# JumpingJack.net
KiCad netlist of a schematic drawn in EasyEDA Pro
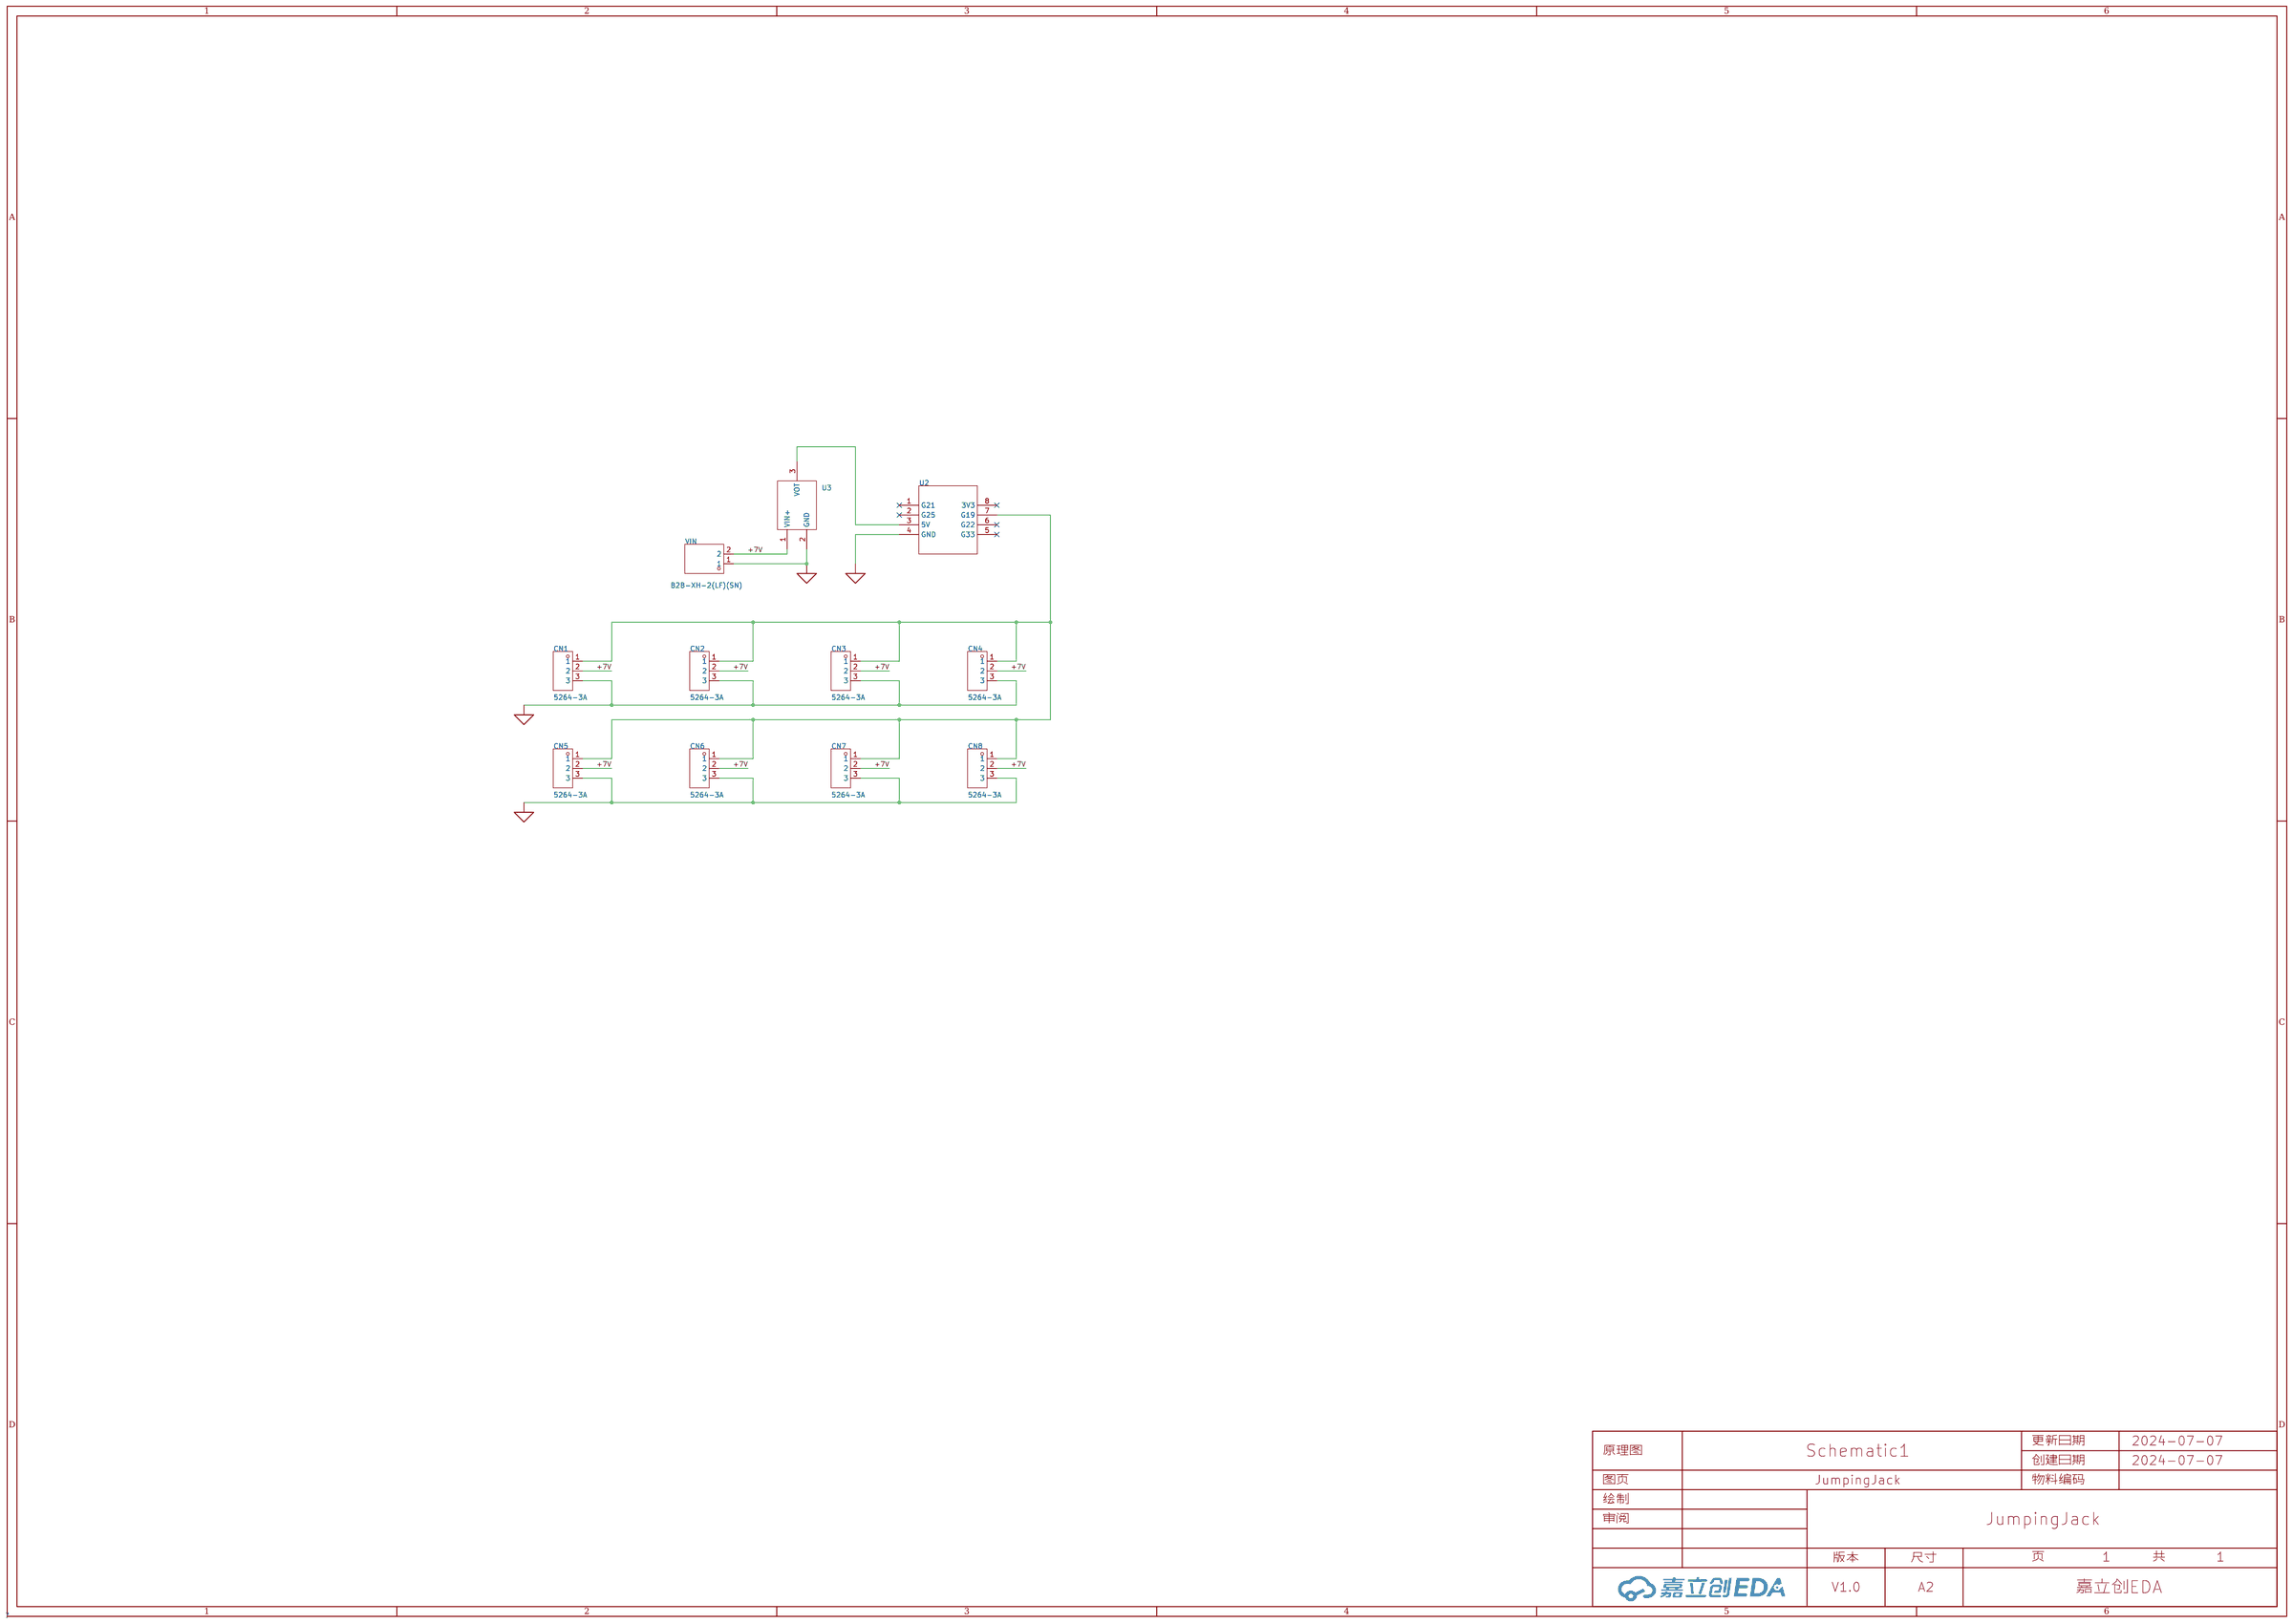
[diagram p0: schematic sheet]

(export (version "E")
  (design (tool "Eeschema 10.0.6"))
  (components
    (comp (ref "CN1")
      (value "5264-3A")
      (footprint "easyedapro:CONN-TH_5264-3A")
      (description "插针结构:1x3P;间距:2.5mm;安装方式:-;参考系列:-;总PIN数:3P;排数:1;每排PIN数:3;行距:-;触头材质:-;")
      (fields (field (name "Manufacturer") "BOOMELE(博穆精密)"))
      (libsource (lib "easyedapro") (part "5264-3A"))
    )
    (comp (ref "CN2")
      (value "5264-3A")
      (footprint "easyedapro:CONN-TH_5264-3A")
      (description "插针结构:1x3P;间距:2.5mm;安装方式:-;参考系列:-;总PIN数:3P;排数:1;每排PIN数:3;行距:-;触头材质:-;")
      (fields (field (name "Manufacturer") "BOOMELE(博穆精密)"))
      (libsource (lib "easyedapro") (part "5264-3A"))
    )
    (comp (ref "CN3")
      (value "5264-3A")
      (footprint "easyedapro:CONN-TH_5264-3A")
      (description "插针结构:1x3P;间距:2.5mm;安装方式:-;参考系列:-;总PIN数:3P;排数:1;每排PIN数:3;行距:-;触头材质:-;")
      (fields (field (name "Manufacturer") "BOOMELE(博穆精密)"))
      (libsource (lib "easyedapro") (part "5264-3A"))
    )
    (comp (ref "CN4")
      (value "5264-3A")
      (footprint "easyedapro:CONN-TH_5264-3A")
      (description "插针结构:1x3P;间距:2.5mm;安装方式:-;参考系列:-;总PIN数:3P;排数:1;每排PIN数:3;行距:-;触头材质:-;")
      (fields (field (name "Manufacturer") "BOOMELE(博穆精密)"))
      (libsource (lib "easyedapro") (part "5264-3A"))
    )
    (comp (ref "CN5")
      (value "5264-3A")
      (footprint "easyedapro:CONN-TH_5264-3A")
      (description "插针结构:1x3P;间距:2.5mm;安装方式:-;参考系列:-;总PIN数:3P;排数:1;每排PIN数:3;行距:-;触头材质:-;")
      (fields (field (name "Manufacturer") "BOOMELE(博穆精密)"))
      (libsource (lib "easyedapro") (part "5264-3A"))
    )
    (comp (ref "CN6")
      (value "5264-3A")
      (footprint "easyedapro:CONN-TH_5264-3A")
      (description "插针结构:1x3P;间距:2.5mm;安装方式:-;参考系列:-;总PIN数:3P;排数:1;每排PIN数:3;行距:-;触头材质:-;")
      (fields (field (name "Manufacturer") "BOOMELE(博穆精密)"))
      (libsource (lib "easyedapro") (part "5264-3A"))
    )
    (comp (ref "CN7")
      (value "5264-3A")
      (footprint "easyedapro:CONN-TH_5264-3A")
      (description "插针结构:1x3P;间距:2.5mm;安装方式:-;参考系列:-;总PIN数:3P;排数:1;每排PIN数:3;行距:-;触头材质:-;")
      (fields (field (name "Manufacturer") "BOOMELE(博穆精密)"))
      (libsource (lib "easyedapro") (part "5264-3A"))
    )
    (comp (ref "CN8")
      (value "5264-3A")
      (footprint "easyedapro:CONN-TH_5264-3A")
      (description "插针结构:1x3P;间距:2.5mm;安装方式:-;参考系列:-;总PIN数:3P;排数:1;每排PIN数:3;行距:-;触头材质:-;")
      (fields (field (name "Manufacturer") "BOOMELE(博穆精密)"))
      (libsource (lib "easyedapro") (part "5264-3A"))
    )
    (comp (ref "U2") (value "~") (libsource (lib "easyedapro") (part "ESP32")))
    (comp (ref "U3") (value "~") (libsource (lib "easyedapro") (part "M78AR05")))
    (comp (ref "VIN")
      (value "B2B-XH-2(LF)(SN)")
      (footprint "easyedapro:CONN-TH_B2B-XH-2-LF-SN")
      (fields (field (name "Manufacturer") "JST"))
      (libsource (lib "easyedapro") (part "B2B-XH-2 (LF)(SN)"))
    )
  )
  (nets
    (net (code "1") (name "/+7V") (class "Default")
      (node (ref "CN1") (pin "2") (pinfunction "2_2") (pintype "unspecified"))
      (node (ref "CN2") (pin "2") (pinfunction "2_2") (pintype "unspecified"))
      (node (ref "CN3") (pin "2") (pinfunction "2_2") (pintype "unspecified"))
      (node (ref "CN4") (pin "2") (pinfunction "2_2") (pintype "unspecified"))
      (node (ref "CN5") (pin "2") (pinfunction "2_2") (pintype "unspecified"))
      (node (ref "CN6") (pin "2") (pinfunction "2_2") (pintype "unspecified"))
      (node (ref "CN7") (pin "2") (pinfunction "2_2") (pintype "unspecified"))
      (node (ref "CN8") (pin "2") (pinfunction "2_2") (pintype "unspecified"))
      (node (ref "U3") (pin "1") (pinfunction "VIN+_1") (pintype "input"))
      (node (ref "VIN") (pin "2") (pinfunction "2_2") (pintype "unspecified"))
    )
    (net (code "2") (name "AGND") (class "Default")
      (node (ref "CN1") (pin "3") (pinfunction "3_3") (pintype "unspecified"))
      (node (ref "CN2") (pin "3") (pinfunction "3_3") (pintype "unspecified"))
      (node (ref "CN3") (pin "3") (pinfunction "3_3") (pintype "unspecified"))
      (node (ref "CN4") (pin "3") (pinfunction "3_3") (pintype "unspecified"))
      (node (ref "CN5") (pin "3") (pinfunction "3_3") (pintype "unspecified"))
      (node (ref "CN6") (pin "3") (pinfunction "3_3") (pintype "unspecified"))
      (node (ref "CN7") (pin "3") (pinfunction "3_3") (pintype "unspecified"))
      (node (ref "CN8") (pin "3") (pinfunction "3_3") (pintype "unspecified"))
      (node (ref "U2") (pin "4") (pinfunction "GND_4") (pintype "input"))
      (node (ref "U3") (pin "2") (pinfunction "GND_2") (pintype "input"))
      (node (ref "VIN") (pin "1") (pinfunction "1_1") (pintype "unspecified"))
    )
    (net (code "3") (name "Net-(U2-5V)") (class "Default")
      (node (ref "U2") (pin "3") (pinfunction "5V_3") (pintype "input"))
      (node (ref "U3") (pin "3") (pinfunction "VOT_3") (pintype "input"))
    )
    (net (code "4") (name "Net-(U2-G19)") (class "Default")
      (node (ref "CN1") (pin "1") (pinfunction "1_1") (pintype "unspecified"))
      (node (ref "CN2") (pin "1") (pinfunction "1_1") (pintype "unspecified"))
      (node (ref "CN3") (pin "1") (pinfunction "1_1") (pintype "unspecified"))
      (node (ref "CN4") (pin "1") (pinfunction "1_1") (pintype "unspecified"))
      (node (ref "CN5") (pin "1") (pinfunction "1_1") (pintype "unspecified"))
      (node (ref "CN6") (pin "1") (pinfunction "1_1") (pintype "unspecified"))
      (node (ref "CN7") (pin "1") (pinfunction "1_1") (pintype "unspecified"))
      (node (ref "CN8") (pin "1") (pinfunction "1_1") (pintype "unspecified"))
      (node (ref "U2") (pin "7") (pinfunction "G19_7") (pintype "input"))
    )
    (net (code "5") (name "unconnected-(U2-3V3-Pad8)") (class "Default")
      (node (ref "U2") (pin "8") (pinfunction "3V3_8") (pintype "input+no_connect"))
    )
    (net (code "6") (name "unconnected-(U2-G21-Pad1)") (class "Default")
      (node (ref "U2") (pin "1") (pinfunction "G21_1") (pintype "input+no_connect"))
    )
    (net (code "7") (name "unconnected-(U2-G22-Pad6)") (class "Default")
      (node (ref "U2") (pin "6") (pinfunction "G22_6") (pintype "input+no_connect"))
    )
    (net (code "8") (name "unconnected-(U2-G25-Pad2)") (class "Default")
      (node (ref "U2") (pin "2") (pinfunction "G25_2") (pintype "input+no_connect"))
    )
    (net (code "9") (name "unconnected-(U2-G33-Pad5)") (class "Default")
      (node (ref "U2") (pin "5") (pinfunction "G33_5") (pintype "input+no_connect"))
    )
  )
)
